# Tomashevich.net
KiCad netlist of a schematic drawn in Altium Designer
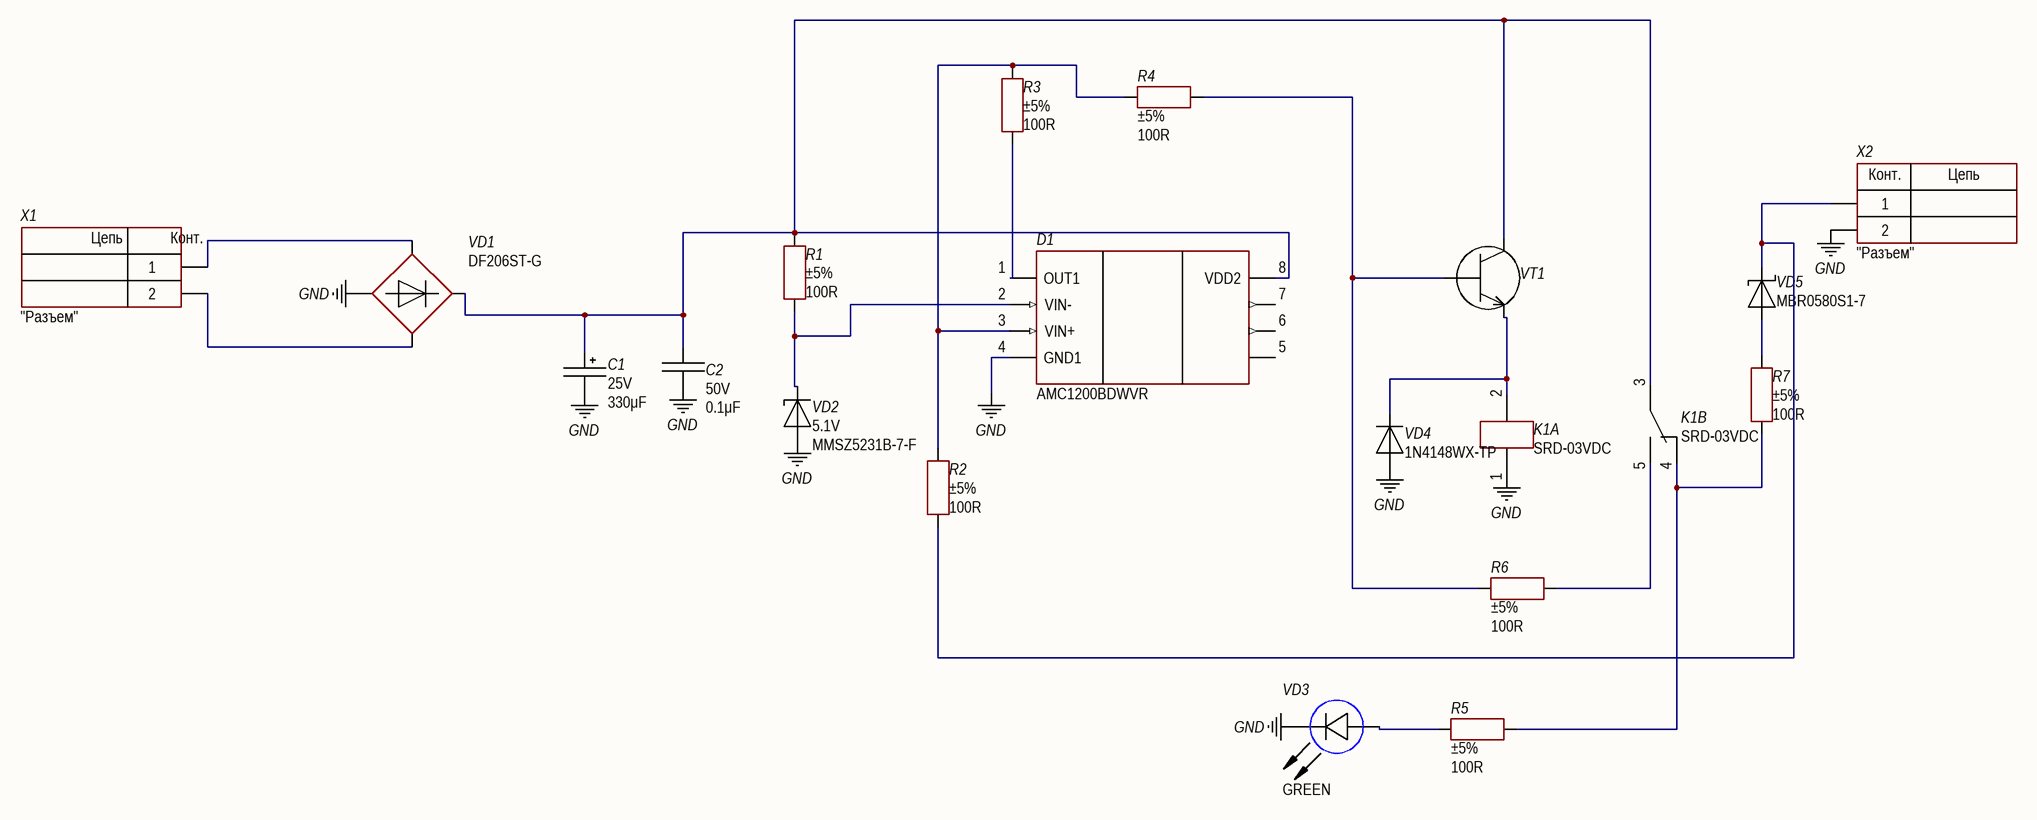
[diagram p0: Tomashevich.SchDoc]

(export (version "E")
  (design (tool "Eeschema 10.0.6"))
  (components
    (comp (ref "C1")
      (value "330μF")
      (footprint "CAP: D6.3C2.5H11")
      (fields
        (field (name "MANUFACTURER") "Wurth")
        (field (name "PARTNUMBER") "860080475013")
        (field (name "VALUEMANUFACTURERPARTNUMBER") "Aluminium capacitor, 330μF, 25V, ±20%, 54mOhm, 14x10x5 mm, -55...+105°C")
        (field (name "VOLTAGE") "25V")
      )
      (libsource (lib "capacitor") (part "Aluminium"))
    )
    (comp (ref "C2")
      (value "0.1μF")
      (footprint "CAP: 1206")
      (fields
        (field (name "MANUFACTURER") "Yageo")
        (field (name "PARTNUMBER") "CC1206KRX7R9BB104")
        (field (name "VALUEMANUFACTURERPARTNUMBER") "Ceramic capacitor, 0.1μF, X7R, ±10%, 50V, 1206, -55...+125°C")
        (field (name "VOLTAGE") "50V")
      )
      (libsource (lib "capacitor") (part "Ceramic_1206"))
    )
    (comp (ref "D1")
      (value "~")
      (footprint "8-SOIC-W")
      (description "Isolator amplifier")
      (fields
        (field (name "MANUFACTURER") "Texas Instruments")
        (field (name "VALUEMANUFACTURERPARTNUMBER") "IC isolator amplifier, Differential, 100 kHz, 2.7...5.5V, -40...+105°C, 8-SOIC")
        (field (name "PARTNUMBER") "AMC1200BDWVR")
      )
      (libsource (lib "ic-amplifier") (part "AMC1200BDWVR"))
    )
    (comp (ref "K1")
      (value "~")
      (footprint "REL: SRD-03VDC")
      (fields
        (field (name "MANUFACTURER") "Ningbo Songle")
        (field (name "VALUEMANUFACTURERPARTNUMBER") "Electromechanics relay, 3VDC, 250VAC, 10A, 1NO, -40...+85°C")
        (field (name "PARTNUMBER") "SRD-03VDC")
      )
      (libsource (lib "") (part "Relay_SRD-03VDC_1"))
    )
    (comp (ref "R1")
      (value "100R")
      (footprint "RES: 1206")
      (fields
        (field (name "MANUFACTURER") "Yageo")
        (field (name "PARTNUMBER") "RC1206JR-07100RL")
        (field (name "VALUEMANUFACTURERPARTNUMBER") "Resistor film, 100R, ±5%, 1206, 0.25W, -55...+125°C")
        (field (name "TOLERANCE") "±5%")
      )
      (libsource (lib "") (part "Resistor_1206_1"))
    )
    (comp (ref "R2")
      (value "100R")
      (footprint "RES: 1206")
      (fields
        (field (name "MANUFACTURER") "Yageo")
        (field (name "PARTNUMBER") "RC1206JR-07100RL")
        (field (name "VALUEMANUFACTURERPARTNUMBER") "Resistor film, 100R, ±5%, 1206, 0.25W, -55...+125°C")
        (field (name "TOLERANCE") "±5%")
      )
      (libsource (lib "") (part "Resistor_1206_1"))
    )
    (comp (ref "R3")
      (value "100R")
      (footprint "RES: 1206")
      (fields
        (field (name "MANUFACTURER") "Yageo")
        (field (name "PARTNUMBER") "RC1206JR-07100RL")
        (field (name "VALUEMANUFACTURERPARTNUMBER") "Resistor film, 100R, ±5%, 1206, 0.25W, -55...+125°C")
        (field (name "TOLERANCE") "±5%")
      )
      (libsource (lib "") (part "Resistor_1206_1"))
    )
    (comp (ref "R4")
      (value "100R")
      (footprint "RES: 1206")
      (fields
        (field (name "MANUFACTURER") "Yageo")
        (field (name "PARTNUMBER") "RC1206JR-07100RL")
        (field (name "VALUEMANUFACTURERPARTNUMBER") "Resistor film, 100R, ±5%, 1206, 0.25W, -55...+125°C")
        (field (name "TOLERANCE") "±5%")
      )
      (libsource (lib "") (part "Resistor_1206_2"))
    )
    (comp (ref "R5")
      (value "100R")
      (footprint "RES: 1206")
      (fields
        (field (name "MANUFACTURER") "Yageo")
        (field (name "PARTNUMBER") "RC1206JR-07100RL")
        (field (name "VALUEMANUFACTURERPARTNUMBER") "Resistor film, 100R, ±5%, 1206, 0.25W, -55...+125°C")
        (field (name "TOLERANCE") "±5%")
      )
      (libsource (lib "resistor") (part "Resistor_1206"))
    )
    (comp (ref "R6")
      (value "100R")
      (footprint "RES: 1206")
      (fields
        (field (name "MANUFACTURER") "Yageo")
        (field (name "PARTNUMBER") "RC1206JR-07100RL")
        (field (name "VALUEMANUFACTURERPARTNUMBER") "Resistor film, 100R, ±5%, 1206, 0.25W, -55...+125°C")
        (field (name "TOLERANCE") "±5%")
      )
      (libsource (lib "resistor") (part "Resistor_1206"))
    )
    (comp (ref "R7")
      (value "100R")
      (footprint "RES: 1206")
      (fields
        (field (name "MANUFACTURER") "Yageo")
        (field (name "PARTNUMBER") "RC1206JR-07100RL")
        (field (name "VALUEMANUFACTURERPARTNUMBER") "Resistor film, 100R, ±5%, 1206, 0.25W, -55...+125°C")
        (field (name "TOLERANCE") "±5%")
      )
      (libsource (lib "") (part "Resistor_1206_1"))
    )
    (comp (ref "VD1")
      (value "~")
      (footprint "DIODE: CD-MBL2")
      (fields
        (field (name "MANUFACTURER") "Comchip Technology")
        (field (name "VALUEMANUFACTURERPARTNUMBER") "Single phase rectifier, 600V, 2A, 1.1V, 4-SMD, -55...+150°C")
        (field (name "VOLTAGE") "600V")
        (field (name "PARTNUMBER") "DF206ST-G")
      )
      (libsource (lib "diode") (part "1PH rectifier"))
    )
    (comp (ref "VD2")
      (value "~")
      (footprint "DIODE: SMA")
      (fields
        (field (name "MANUFACTURER") "Diodes Incorporated")
        (field (name "VALUEMANUFACTURERPARTNUMBER") "Zener diode, 5.1V, 500mW, 0.9V, 17Ohm, SOD-123, -55...+150°C")
        (field (name "VOLTAGE") "5.1V")
        (field (name "PARTNUMBER") "MMSZ5231B-7-F")
      )
      (libsource (lib "diode") (part "Zener_single"))
    )
    (comp (ref "VD3")
      (value "~")
      (footprint "LED: 1206G")
      (fields
        (field (name "VALUEMANUFACTURERPARTNUMBER") "LED, Green, *, *, *, -55...+150°C")
        (field (name "COLOR") "GREEN")
      )
      (libsource (lib "diode") (part "LED_single"))
    )
    (comp (ref "VD4")
      (value "~")
      (footprint "DIODE: SMA")
      (fields
        (field (name "MANUFACTURER") "Micro Commercial")
        (field (name "VALUEMANUFACTURERPARTNUMBER") "Single diode, 75V, 150mA, 1V, 4ns, SOD-323, -55...+150°C")
        (field (name "VOLTAGE") "75V")
        (field (name "PARTNUMBER") "1N4148WX-TP")
      )
      (libsource (lib "diode") (part "Diode_single"))
    )
    (comp (ref "VD5")
      (value "~")
      (footprint "DIODE: SMA")
      (fields
        (field (name "MANUFACTURER") "Diodes Incorporated")
        (field (name "VALUEMANUFACTURERPARTNUMBER") "Schottky diode, 80V, 500mA, 1V, 15pF, SOD-123, -55...+150°C")
        (field (name "VOLTAGE") "80V")
        (field (name "PARTNUMBER") "MBR0580S1-7")
      )
      (libsource (lib "diode") (part "Schottky_single"))
    )
    (comp (ref "VT1")
      (value "transistor")
      (footprint "TO247")
      (libsource (lib "Schlib1") (part "transistor"))
    )
    (comp (ref "X1")
      (value "~")
      (footprint "CON: CWF-2")
      (fields
        (field (name "MANUFACTURER") "Connfly")
        (field (name "VALUEMANUFACTURERPARTNUMBER") "Connector, 2pin, 2.54mm, 250VAC, 3A")
        (field (name "PARTNUMBER") "CWF-2R")
        (field (name "COMMENTTEXT") "\"Разъем\"")
      )
      (libsource (lib "") (part "CWF-2_1"))
    )
    (comp (ref "X2")
      (value "~")
      (footprint "CON: CWF-2")
      (fields
        (field (name "MANUFACTURER") "Connfly")
        (field (name "VALUEMANUFACTURERPARTNUMBER") "Connector, 2pin, 2.54mm, 250VAC, 3A")
        (field (name "PARTNUMBER") "CWF-2R")
        (field (name "COMMENTTEXT") "\"Разъем\"")
      )
      (libsource (lib "connector") (part "CWF-2"))
    )
  )
  (nets
    (net (code "1") (name "GND") (class "Default")
      (node (ref "C1") (pin "2") (pinfunction "2_2") (pintype "passive"))
      (node (ref "C2") (pin "1") (pinfunction "1_1") (pintype "passive"))
      (node (ref "D1") (pin "4") (pinfunction "GND1_4") (pintype "power_in"))
      (node (ref "K1") (pin "1") (pinfunction "1_1") (pintype "passive"))
      (node (ref "VD1") (pin "1") (pinfunction "1_1") (pintype "passive"))
      (node (ref "VD2") (pin "1") (pinfunction "A_1") (pintype "passive"))
      (node (ref "VD3") (pin "2") (pinfunction "C_2") (pintype "passive"))
      (node (ref "VD4") (pin "1") (pinfunction "1_1") (pintype "passive"))
      (node (ref "X2") (pin "2") (pinfunction "2_2") (pintype "passive"))
    )
    (net (code "2") (name "Net-(D1-OUT1)") (class "Default")
      (node (ref "D1") (pin "1") (pinfunction "OUT1_1") (pintype "power_in"))
      (node (ref "R3") (pin "1") (pinfunction "1_1") (pintype "passive"))
    )
    (net (code "3") (name "Net-(D1-VDD2)") (class "Default")
      (node (ref "C1") (pin "1") (pinfunction "1_1") (pintype "passive"))
      (node (ref "C2") (pin "2") (pinfunction "2_2") (pintype "passive"))
      (node (ref "D1") (pin "8") (pinfunction "VDD2_8") (pintype "power_in"))
      (node (ref "K1") (pin "3") (pinfunction "3_3") (pintype "passive"))
      (node (ref "R1") (pin "2") (pinfunction "2_2") (pintype "passive"))
      (node (ref "VD1") (pin "3") (pinfunction "3_3") (pintype "passive"))
      (node (ref "VT1") (pin "3") (pinfunction "3_3") (pintype "passive"))
    )
    (net (code "4") (name "Net-(D1-VIN+)") (class "Default")
      (node (ref "D1") (pin "3") (pinfunction "VIN+_3") (pintype "input"))
      (node (ref "R2") (pin "2") (pinfunction "2_2") (pintype "passive"))
      (node (ref "R3") (pin "2") (pinfunction "2_2") (pintype "passive"))
      (node (ref "R4") (pin "2") (pinfunction "2_2") (pintype "passive"))
    )
    (net (code "5") (name "Net-(D1-VIN-)") (class "Default")
      (node (ref "D1") (pin "2") (pinfunction "VIN-_2") (pintype "input"))
      (node (ref "R1") (pin "1") (pinfunction "1_1") (pintype "passive"))
      (node (ref "VD2") (pin "2") (pinfunction "C_2") (pintype "passive"))
    )
    (net (code "6") (name "Net-(K1-Pad2)") (class "Default")
      (node (ref "K1") (pin "2") (pinfunction "2_2") (pintype "passive"))
      (node (ref "VD4") (pin "2") (pinfunction "2_2") (pintype "passive"))
      (node (ref "VT1") (pin "2") (pinfunction "2_2") (pintype "passive"))
    )
    (net (code "7") (name "Net-(K1-Pad4)") (class "Default")
      (node (ref "K1") (pin "4") (pinfunction "4_4") (pintype "passive"))
      (node (ref "R5") (pin "1") (pinfunction "1_1") (pintype "passive"))
      (node (ref "R7") (pin "1") (pinfunction "1_1") (pintype "passive"))
    )
    (net (code "8") (name "Net-(K1-Pad5)") (class "Default")
      (node (ref "K1") (pin "5") (pinfunction "5_5") (pintype "passive"))
      (node (ref "R6") (pin "1") (pinfunction "1_1") (pintype "passive"))
    )
    (net (code "9") (name "Net-(R2-Pad1)") (class "Default")
      (node (ref "R2") (pin "1") (pinfunction "1_1") (pintype "passive"))
      (node (ref "VD5") (pin "2") (pinfunction "2_2") (pintype "passive"))
      (node (ref "X2") (pin "1") (pinfunction "1_1") (pintype "passive"))
    )
    (net (code "10") (name "Net-(R4-Pad1)") (class "Default")
      (node (ref "R4") (pin "1") (pinfunction "1_1") (pintype "passive"))
      (node (ref "R6") (pin "2") (pinfunction "2_2") (pintype "passive"))
      (node (ref "VT1") (pin "1") (pinfunction "1_1") (pintype "passive"))
    )
    (net (code "11") (name "Net-(R7-Pad2)") (class "Default")
      (node (ref "R7") (pin "2") (pinfunction "2_2") (pintype "passive"))
      (node (ref "VD5") (pin "1") (pinfunction "1_1") (pintype "passive"))
    )
    (net (code "12") (name "Net-(VD1-Pad2)") (class "Default")
      (node (ref "VD1") (pin "2") (pinfunction "2_2") (pintype "passive"))
      (node (ref "X1") (pin "1") (pinfunction "1_1") (pintype "passive"))
    )
    (net (code "13") (name "Net-(VD1-Pad4)") (class "Default")
      (node (ref "VD1") (pin "4") (pinfunction "4_4") (pintype "passive"))
      (node (ref "X1") (pin "2") (pinfunction "2_2") (pintype "passive"))
    )
    (net (code "14") (name "Net-(VD3-A)") (class "Default")
      (node (ref "R5") (pin "2") (pinfunction "2_2") (pintype "passive"))
      (node (ref "VD3") (pin "1") (pinfunction "A_1") (pintype "passive"))
    )
    (net (code "15") (name "unconnected-(D1-Pad5)") (class "Default")
      (node (ref "D1") (pin "5") (pintype "power_in"))
    )
    (net (code "16") (name "unconnected-(D1-Pad6)") (class "Default")
      (node (ref "D1") (pin "6") (pintype "output"))
    )
    (net (code "17") (name "unconnected-(D1-Pad7)") (class "Default")
      (node (ref "D1") (pin "7") (pintype "output"))
    )
  )
)
